# HolmesAndWatchson-BASIC-TOP.net
KiCad netlist of a schematic drawn in EAGLE
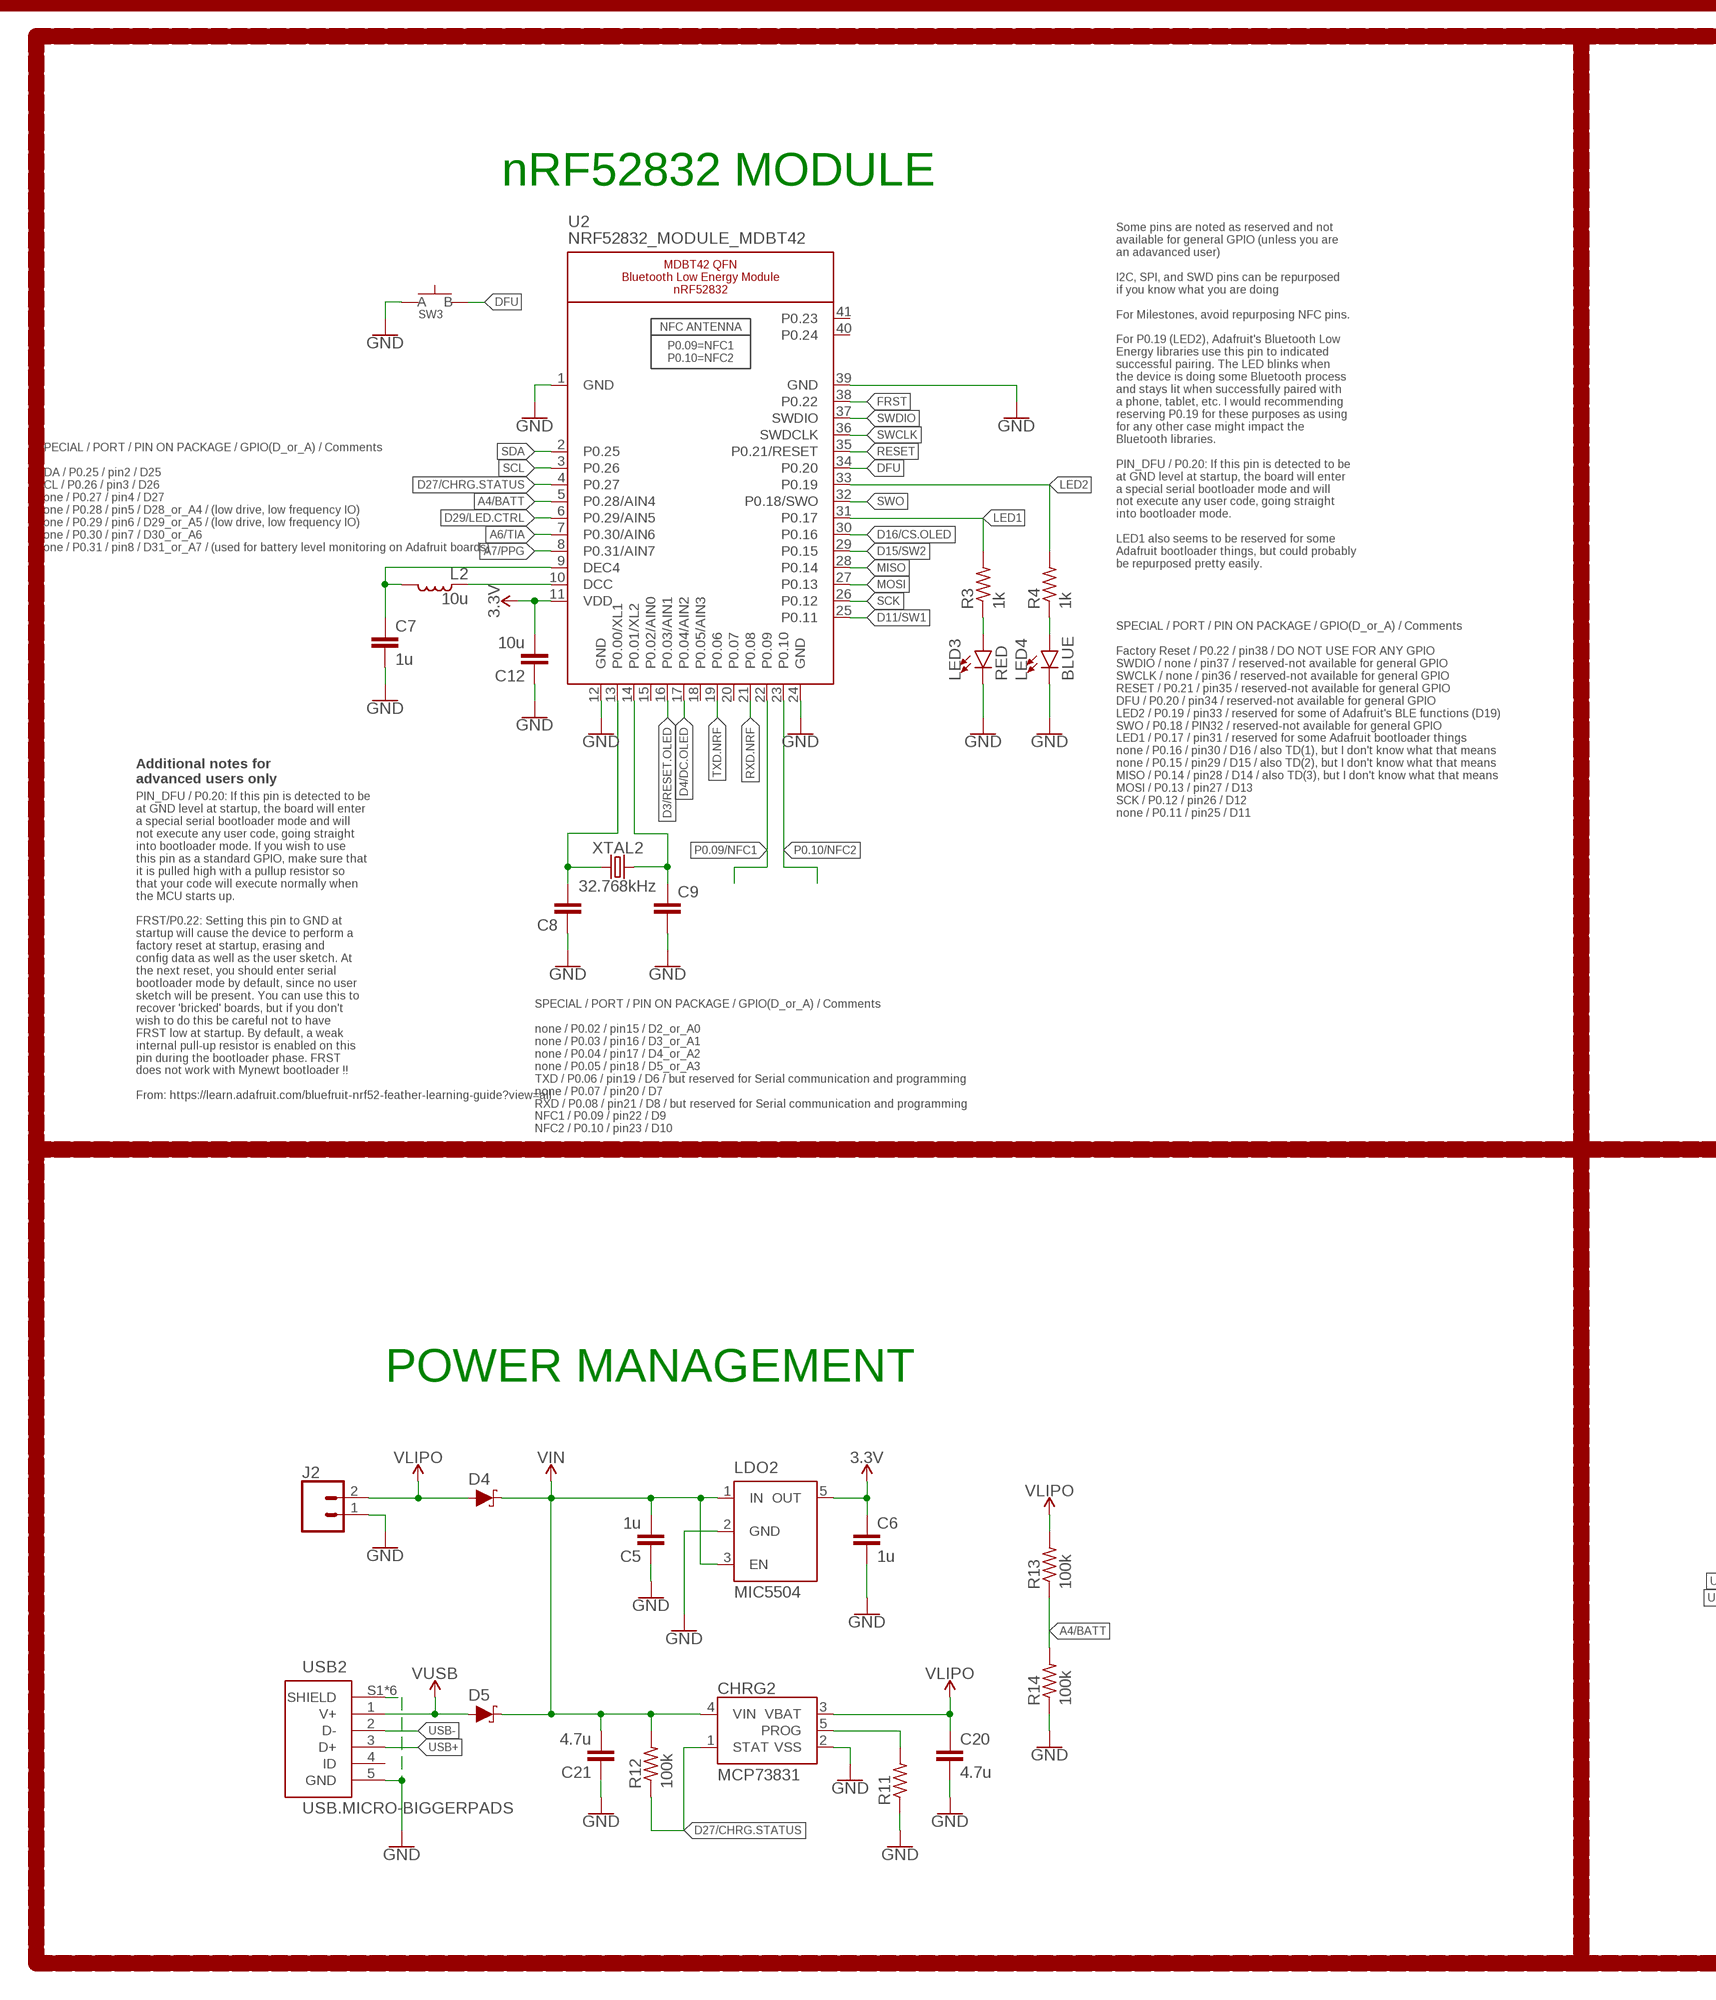
[diagram p0: schematic, sheet 1, part 1 of 2]
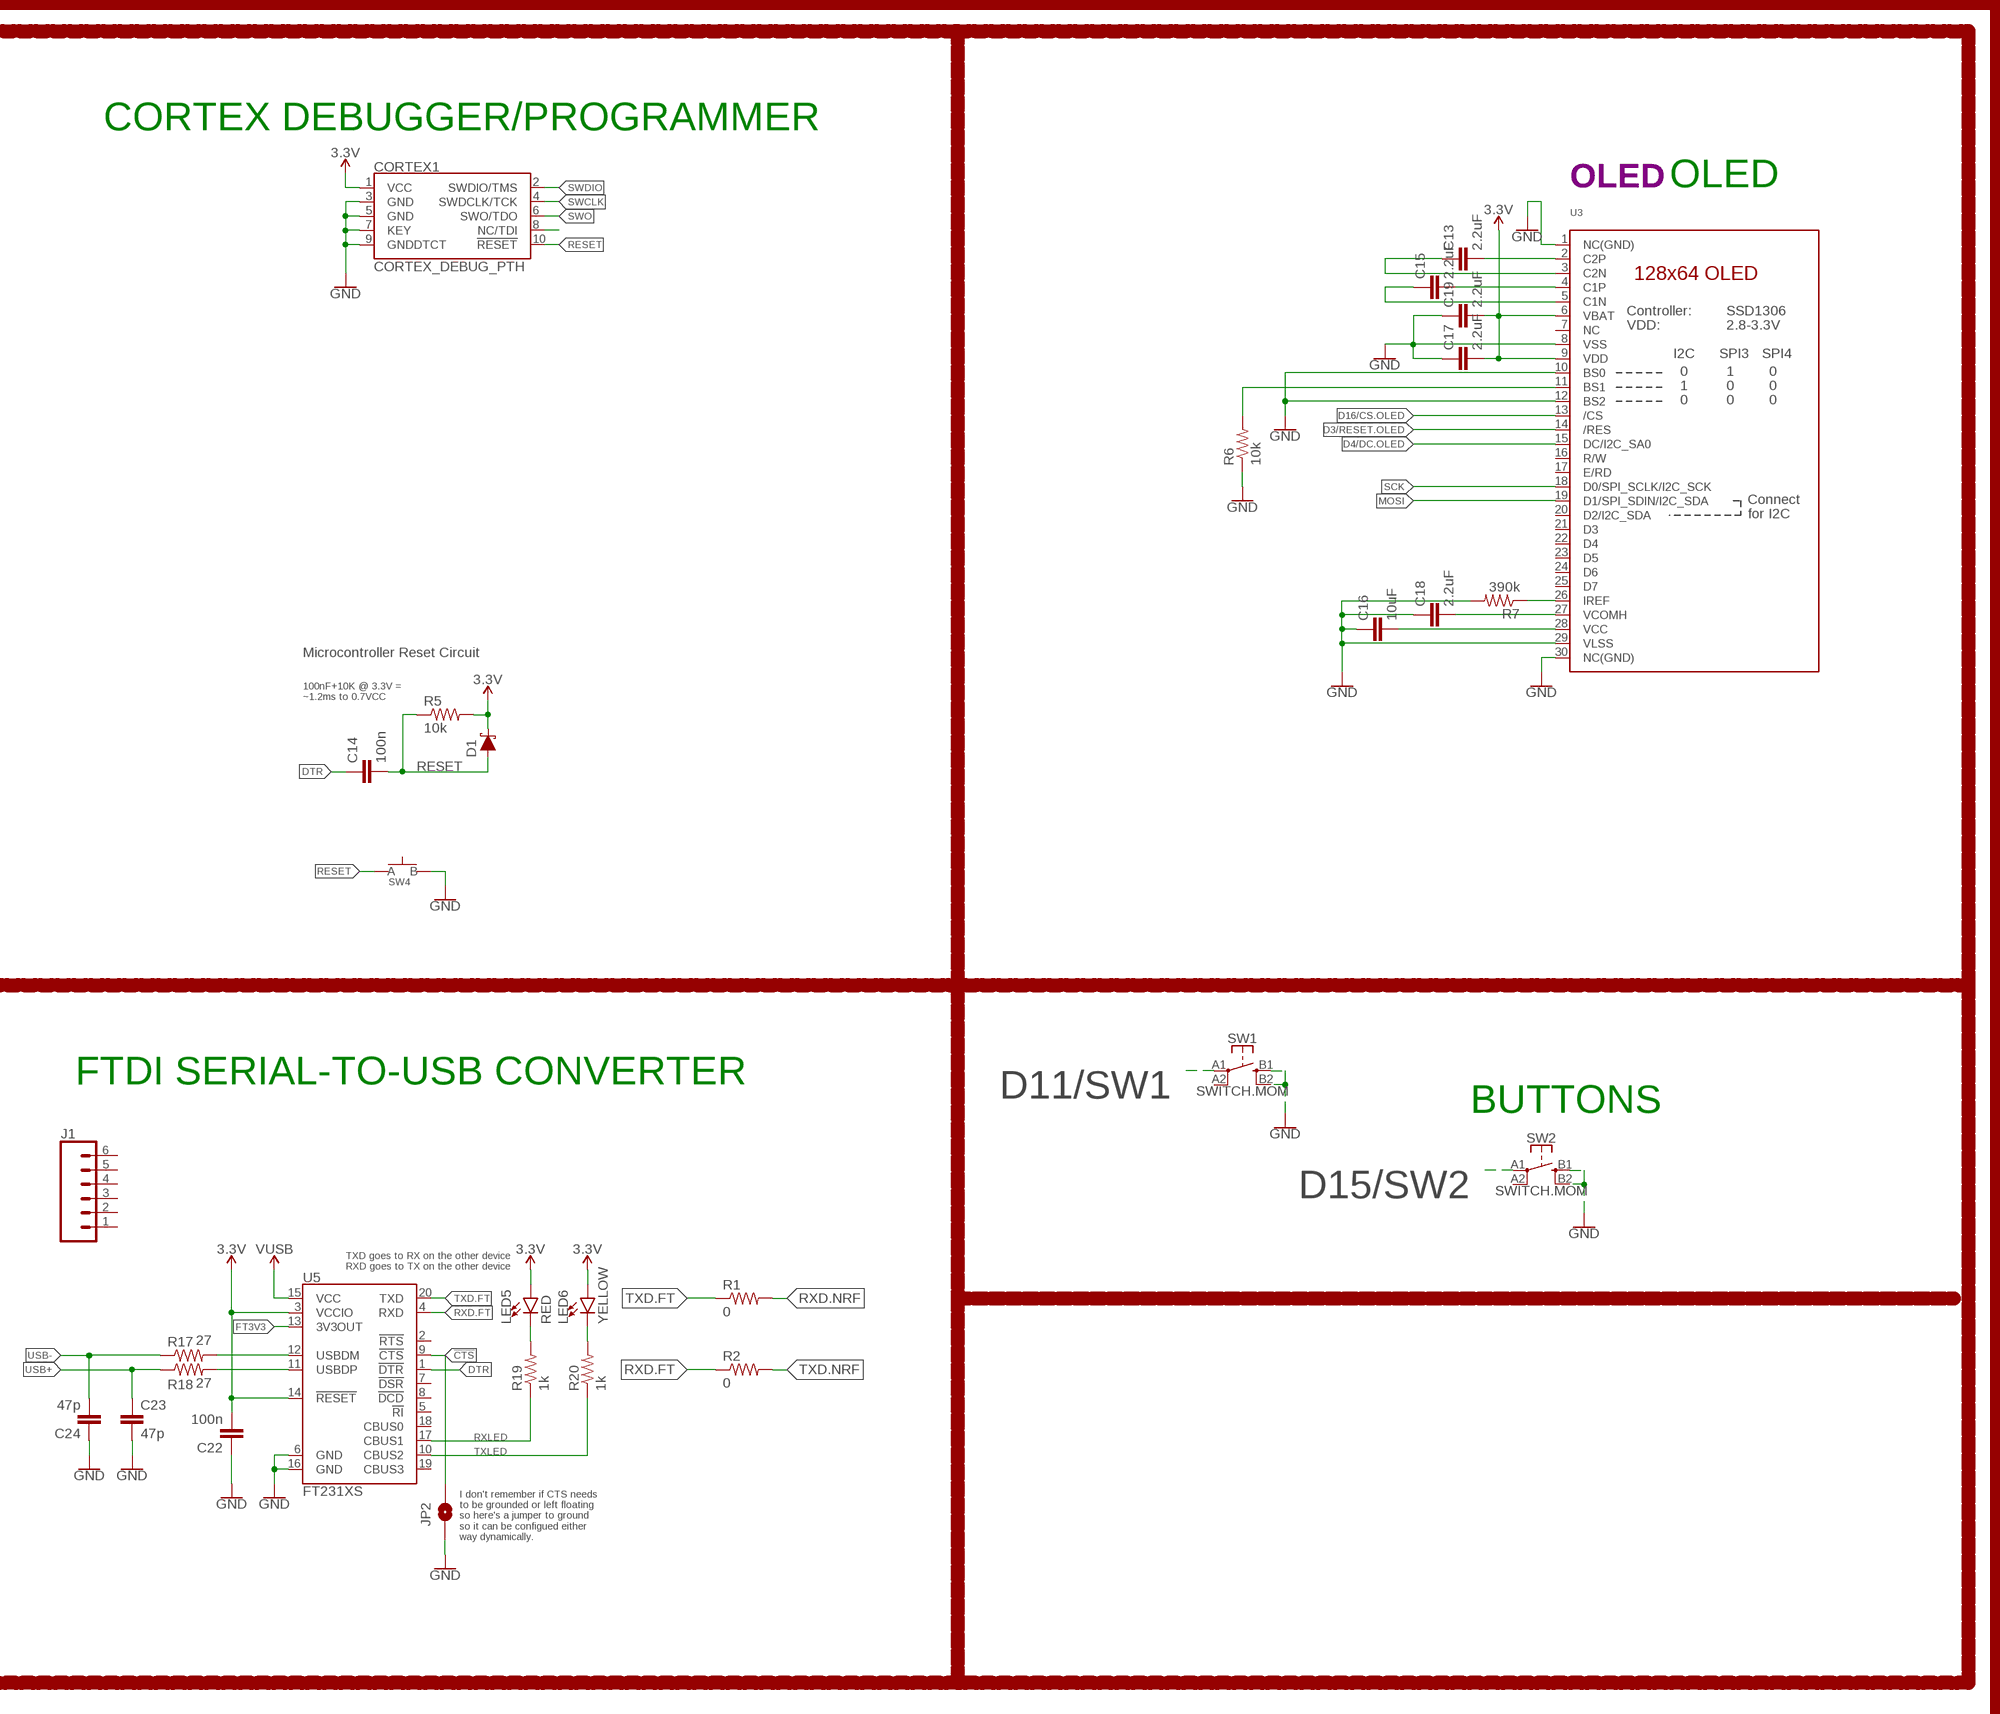
[diagram p1: schematic, sheet 1, part 2 of 2]

(export (version "E")
  (design (tool "Eeschema 10.0.6"))
  (components
    (comp (ref "C5")
      (value "1u")
      (footprint "eagle-import:C0603")
      (libsource (lib "eagle-import") (part "CAPACITOR0603"))
    )
    (comp (ref "C6")
      (value "1u")
      (footprint "eagle-import:C0603")
      (libsource (lib "eagle-import") (part "CAPACITOR0603"))
    )
    (comp (ref "C7")
      (value "1u")
      (footprint "eagle-import:C0603")
      (libsource (lib "eagle-import") (part "CAPACITOR0603"))
    )
    (comp (ref "C8")
      (value "CAPACITOR0603")
      (footprint "eagle-import:C0603")
      (libsource (lib "eagle-import") (part "CAPACITOR0603"))
    )
    (comp (ref "C9")
      (value "CAPACITOR0603")
      (footprint "eagle-import:C0603")
      (libsource (lib "eagle-import") (part "CAPACITOR0603"))
    )
    (comp (ref "C12")
      (value "10u")
      (footprint "eagle-import:C0805")
      (libsource (lib "eagle-import") (part "CAPACITOR0805"))
    )
    (comp (ref "C13")
      (value "2.2uF")
      (footprint "eagle-import:C0402")
      (libsource (lib "eagle-import") (part "CAPACITOR0402"))
    )
    (comp (ref "C14")
      (value "100n")
      (footprint "eagle-import:C0603")
      (libsource (lib "eagle-import") (part "CAPACITOR0603"))
    )
    (comp (ref "C15")
      (value "2.2uF")
      (footprint "eagle-import:C0402")
      (libsource (lib "eagle-import") (part "CAPACITOR0402"))
    )
    (comp (ref "C16")
      (value "10uF")
      (footprint "eagle-import:C0603")
      (libsource (lib "eagle-import") (part "CAPACITOR0603"))
    )
    (comp (ref "C17")
      (value "2.2uF")
      (footprint "eagle-import:C0402")
      (libsource (lib "eagle-import") (part "CAPACITOR0402"))
    )
    (comp (ref "C18")
      (value "2.2uF")
      (footprint "eagle-import:C0402")
      (libsource (lib "eagle-import") (part "CAPACITOR0402"))
    )
    (comp (ref "C19")
      (value "2.2uF")
      (footprint "eagle-import:C0402")
      (libsource (lib "eagle-import") (part "CAPACITOR0402"))
    )
    (comp (ref "C20")
      (value "4.7u")
      (footprint "eagle-import:C0603")
      (libsource (lib "eagle-import") (part "CAPACITOR0603"))
    )
    (comp (ref "C21")
      (value "4.7u")
      (footprint "eagle-import:C0603")
      (libsource (lib "eagle-import") (part "CAPACITOR0603"))
    )
    (comp (ref "C22")
      (value "100n")
      (footprint "eagle-import:C0603")
      (libsource (lib "eagle-import") (part "CAPACITOR0603"))
    )
    (comp (ref "C23")
      (value "47p")
      (footprint "eagle-import:C0603")
      (libsource (lib "eagle-import") (part "CAPACITOR0603"))
    )
    (comp (ref "C24")
      (value "47p")
      (footprint "eagle-import:C0603")
      (libsource (lib "eagle-import") (part "CAPACITOR0603"))
    )
    (comp (ref "CHRG2")
      (value "MCP73831")
      (footprint "eagle-import:SOT23-5")
      (libsource (lib "eagle-import") (part "MCP73831"))
    )
    (comp (ref "CORTEX1")
      (value "CORTEX_DEBUG_PTH")
      (footprint "eagle-import:2X5-PTH-1.27MM")
      (libsource (lib "eagle-import") (part "CORTEX_DEBUG_PTH"))
    )
    (comp (ref "D1")
      (value "SCHOTTKY-USC")
      (footprint "eagle-import:USC")
      (libsource (lib "eagle-import") (part "SCHOTTKY-USC"))
    )
    (comp (ref "D4")
      (value "SCHOTTKY-USC")
      (footprint "eagle-import:USC")
      (libsource (lib "eagle-import") (part "SCHOTTKY-USC"))
    )
    (comp (ref "D5")
      (value "SCHOTTKY-USC")
      (footprint "eagle-import:USC")
      (libsource (lib "eagle-import") (part "SCHOTTKY-USC"))
    )
    (comp (ref "J1")
      (value "CONN_061.27MM")
      (footprint "eagle-import:1X06_1.27MM")
      (libsource (lib "eagle-import") (part "CONN_061.27MM"))
    )
    (comp (ref "J2")
      (value "CONN_02")
      (footprint "eagle-import:1X02")
      (libsource (lib "eagle-import") (part "CONN_02"))
    )
    (comp (ref "JP2")
      (value "JUMPER-SMT_2_NO_SILK")
      (footprint "eagle-import:SMT-JUMPER_2_NO_SILK")
      (libsource (lib "eagle-import") (part "JUMPER-SMT_2_NO_SILK"))
    )
    (comp (ref "L2")
      (value "10u")
      (footprint "eagle-import:L0603")
      (libsource (lib "eagle-import") (part "INDUCTOR0603"))
    )
    (comp (ref "LDO2")
      (value "MIC5504")
      (footprint "eagle-import:SOT23-5")
      (libsource (lib "eagle-import") (part "MIC5504"))
    )
    (comp (ref "LED3")
      (value "RED")
      (footprint "eagle-import:LED-0603")
      (libsource (lib "eagle-import") (part "LED0603"))
    )
    (comp (ref "LED4")
      (value "BLUE")
      (footprint "eagle-import:LED-0603")
      (libsource (lib "eagle-import") (part "LED0603"))
    )
    (comp (ref "LED5")
      (value "RED")
      (footprint "eagle-import:LED-0603")
      (libsource (lib "eagle-import") (part "LED0603"))
    )
    (comp (ref "LED6")
      (value "YELLOW")
      (footprint "eagle-import:LED-0603")
      (libsource (lib "eagle-import") (part "LED0603"))
    )
    (comp (ref "R1")
      (value "0")
      (footprint "eagle-import:R0603")
      (libsource (lib "eagle-import") (part "RESISTOR0603"))
    )
    (comp (ref "R2")
      (value "0")
      (footprint "eagle-import:R0603")
      (libsource (lib "eagle-import") (part "RESISTOR0603"))
    )
    (comp (ref "R3")
      (value "1k")
      (footprint "eagle-import:R0603")
      (libsource (lib "eagle-import") (part "RESISTOR0603"))
    )
    (comp (ref "R4")
      (value "1k")
      (footprint "eagle-import:R0603")
      (libsource (lib "eagle-import") (part "RESISTOR0603"))
    )
    (comp (ref "R5")
      (value "10k")
      (footprint "eagle-import:R0603")
      (libsource (lib "eagle-import") (part "RESISTOR0603"))
    )
    (comp (ref "R6")
      (value "10k")
      (footprint "eagle-import:R0603")
      (libsource (lib "eagle-import") (part "RESISTOR0603"))
    )
    (comp (ref "R7")
      (value "390k")
      (footprint "eagle-import:R0603")
      (libsource (lib "eagle-import") (part "RESISTOR0603"))
    )
    (comp (ref "R11")
      (value "RESISTOR0603")
      (footprint "eagle-import:R0603")
      (libsource (lib "eagle-import") (part "RESISTOR0603"))
    )
    (comp (ref "R12")
      (value "100k")
      (footprint "eagle-import:R0603")
      (libsource (lib "eagle-import") (part "RESISTOR0603"))
    )
    (comp (ref "R13")
      (value "100k")
      (footprint "eagle-import:R0603")
      (libsource (lib "eagle-import") (part "RESISTOR0603"))
    )
    (comp (ref "R14")
      (value "100k")
      (footprint "eagle-import:R0603")
      (libsource (lib "eagle-import") (part "RESISTOR0603"))
    )
    (comp (ref "R17")
      (value "27")
      (footprint "eagle-import:R0603")
      (libsource (lib "eagle-import") (part "RESISTOR0603"))
    )
    (comp (ref "R18")
      (value "27")
      (footprint "eagle-import:R0603")
      (libsource (lib "eagle-import") (part "RESISTOR0603"))
    )
    (comp (ref "R19")
      (value "1k")
      (footprint "eagle-import:R0603")
      (libsource (lib "eagle-import") (part "RESISTOR0603"))
    )
    (comp (ref "R20")
      (value "1k")
      (footprint "eagle-import:R0603")
      (libsource (lib "eagle-import") (part "RESISTOR0603"))
    )
    (comp (ref "SW1")
      (value "SWITCH.MOM")
      (footprint "eagle-import:TACTILE_SWITCH_SMD_6.2MM_TALL")
      (libsource (lib "eagle-import") (part "SWITCH.MOM"))
    )
    (comp (ref "SW2")
      (value "SWITCH.MOM")
      (footprint "eagle-import:TACTILE_SWITCH_SMD_6.2MM_TALL")
      (libsource (lib "eagle-import") (part "SWITCH.MOM"))
    )
    (comp (ref "SW3")
      (value "SPST-PTS830GG140-COPY.1-3")
      (footprint "eagle-import:BUTTON-GULLWING")
      (libsource (lib "eagle-import") (part "SPST-PTS830GG140-COPY.1-3"))
    )
    (comp (ref "SW4")
      (value "SPST-PTS830GG140-COPY.1-3")
      (footprint "eagle-import:BUTTON-GULLWING")
      (libsource (lib "eagle-import") (part "SPST-PTS830GG140-COPY.1-3"))
    )
    (comp (ref "U2")
      (value "NRF52832_MODULE_MDBT42")
      (footprint "eagle-import:BLE_MODULE_RAYTAC_MDBT42")
      (libsource (lib "eagle-import") (part "NRF52832_MODULE_MDBT42"))
    )
    (comp (ref "U3")
      (value "DISP_OLED_UG-2864HSWEG01-NO-WRAPAROUND")
      (footprint "eagle-import:UG-2864HSWEG01_0.96IN_NO-WRAPAROUND")
      (libsource (lib "eagle-import") (part "DISP_OLED_UG-2864HSWEG01-NO-WRAPAROUND"))
    )
    (comp (ref "U5")
      (value "FT231XS")
      (footprint "eagle-import:SSOP20_L")
      (libsource (lib "eagle-import") (part "FT231XS"))
    )
    (comp (ref "USB2")
      (value "USB.MICRO-BIGGERPADS")
      (footprint "eagle-import:USB-MICRO-01.BIGGERPADS")
      (libsource (lib "eagle-import") (part "USB.MICRO-BIGGERPADS"))
    )
    (comp (ref "XTAL2")
      (value "32.768kHz")
      (footprint "eagle-import:2-SMD.NOLEAD.2.0MMTO1.2MM")
      (libsource (lib "eagle-import") (part "CRYSTALECS-.327-12.5-12-C-TR"))
    )
  )
  (nets
    (net (code "1") (name "/RXLED") (class "Default")
      (node (ref "R19") (pin "1") (pinfunction "1_1") (pintype "passive"))
      (node (ref "U5") (pin "17") (pinfunction "CBUS1_17") (pintype "bidirectional"))
    )
    (net (code "2") (name "/TXLED") (class "Default")
      (node (ref "R20") (pin "1") (pinfunction "1_1") (pintype "passive"))
      (node (ref "U5") (pin "10") (pinfunction "CBUS2_10") (pintype "bidirectional"))
    )
    (net (code "3") (name "/~{CTS}") (class "Default")
      (node (ref "JP2") (pin "2") (pinfunction "2_2") (pintype "passive"))
      (node (ref "U5") (pin "9") (pinfunction "~{CTS}_9") (pintype "bidirectional"))
    )
    (net (code "4") (name "3.3V") (class "Default")
      (node (ref "C12") (pin "2") (pinfunction "2_2") (pintype "passive"))
      (node (ref "C17") (pin "2") (pinfunction "2_2") (pintype "passive"))
      (node (ref "C19") (pin "2") (pinfunction "2_2") (pintype "passive"))
      (node (ref "C22") (pin "2") (pinfunction "2_2") (pintype "passive"))
      (node (ref "C6") (pin "1") (pinfunction "1_1") (pintype "passive"))
      (node (ref "CORTEX1") (pin "1") (pinfunction "VCC_1") (pintype "bidirectional"))
      (node (ref "D1") (pin "-") (pinfunction "C_-") (pintype "passive"))
      (node (ref "LDO2") (pin "5") (pinfunction "OUT_5") (pintype "bidirectional"))
      (node (ref "LED5") (pin "A") (pinfunction "A_A") (pintype "passive"))
      (node (ref "LED6") (pin "A") (pinfunction "A_A") (pintype "passive"))
      (node (ref "R5") (pin "2") (pinfunction "2_2") (pintype "passive"))
      (node (ref "U2") (pin "11") (pinfunction "VDD_11") (pintype "bidirectional"))
      (node (ref "U3") (pin "6") (pinfunction "VBAT_6") (pintype "input"))
      (node (ref "U3") (pin "9") (pinfunction "VDD_9") (pintype "power_in"))
      (node (ref "U5") (pin "14") (pinfunction "~{RESET}_14") (pintype "bidirectional"))
      (node (ref "U5") (pin "3") (pinfunction "VCCIO_3") (pintype "bidirectional"))
    )
    (net (code "5") (name "A4{slash}BATT") (class "Default")
      (node (ref "R13") (pin "1") (pinfunction "1_1") (pintype "passive"))
      (node (ref "R14") (pin "2") (pinfunction "2_2") (pintype "passive"))
      (node (ref "U2") (pin "5") (pinfunction "P0.28/AIN4_5") (pintype "bidirectional"))
    )
    (net (code "6") (name "A6{slash}TIA") (class "Default")
      (node (ref "U2") (pin "7") (pinfunction "P0.30/AIN6_7") (pintype "bidirectional"))
    )
    (net (code "7") (name "A7{slash}PPG") (class "Default")
      (node (ref "U2") (pin "8") (pinfunction "P0.31/AIN7_8") (pintype "bidirectional"))
    )
    (net (code "8") (name "D3{slash}RESET.OLED") (class "Default")
      (node (ref "U2") (pin "16") (pinfunction "P0.03/AIN1_16") (pintype "bidirectional"))
      (node (ref "U3") (pin "14") (pinfunction "/RES_14") (pintype "input"))
    )
    (net (code "9") (name "D4{slash}DC.OLED") (class "Default")
      (node (ref "U2") (pin "17") (pinfunction "P0.04/AIN2_17") (pintype "bidirectional"))
      (node (ref "U3") (pin "15") (pinfunction "DC/I2C_SA0_15") (pintype "input"))
    )
    (net (code "10") (name "D11{slash}SW1") (class "Default")
      (node (ref "SW1") (pin "A1") (pinfunction "1_A1") (pintype "passive"))
      (node (ref "U2") (pin "25") (pinfunction "P0.11_25") (pintype "bidirectional"))
    )
    (net (code "11") (name "D15{slash}SW2") (class "Default")
      (node (ref "SW2") (pin "A1") (pinfunction "1_A1") (pintype "passive"))
      (node (ref "U2") (pin "29") (pinfunction "P0.15_29") (pintype "bidirectional"))
    )
    (net (code "12") (name "D16{slash}CS.OLED") (class "Default")
      (node (ref "U2") (pin "30") (pinfunction "P0.16_30") (pintype "bidirectional"))
      (node (ref "U3") (pin "13") (pinfunction "/CS_13") (pintype "input"))
    )
    (net (code "13") (name "D27{slash}CHRG.STATUS") (class "Default")
      (node (ref "CHRG2") (pin "1") (pinfunction "STAT_1") (pintype "output"))
      (node (ref "R12") (pin "1") (pinfunction "1_1") (pintype "passive"))
      (node (ref "U2") (pin "4") (pinfunction "P0.27_4") (pintype "bidirectional"))
    )
    (net (code "14") (name "D29{slash}LED.CTRL") (class "Default")
      (node (ref "U2") (pin "6") (pinfunction "P0.29/AIN5_6") (pintype "bidirectional"))
    )
    (net (code "15") (name "DFU") (class "Default")
      (node (ref "SW3") (pin "3") (pinfunction "B_3") (pintype "bidirectional"))
      (node (ref "U2") (pin "34") (pinfunction "P0.20_34") (pintype "bidirectional"))
    )
    (net (code "16") (name "DTR") (class "Default")
      (node (ref "C14") (pin "1") (pinfunction "1_1") (pintype "passive"))
      (node (ref "U5") (pin "1") (pinfunction "~{DTR}_1") (pintype "bidirectional"))
    )
    (net (code "17") (name "FRST") (class "Default")
      (node (ref "U2") (pin "38") (pinfunction "P0.22_38") (pintype "bidirectional"))
    )
    (net (code "18") (name "FT3V3") (class "Default")
      (node (ref "U5") (pin "13") (pinfunction "3V3OUT_13") (pintype "bidirectional"))
    )
    (net (code "19") (name "GND") (class "Default")
      (node (ref "C12") (pin "1") (pinfunction "1_1") (pintype "passive"))
      (node (ref "C16") (pin "1") (pinfunction "1_1") (pintype "passive"))
      (node (ref "C17") (pin "1") (pinfunction "1_1") (pintype "passive"))
      (node (ref "C18") (pin "1") (pinfunction "1_1") (pintype "passive"))
      (node (ref "C19") (pin "1") (pinfunction "1_1") (pintype "passive"))
      (node (ref "C20") (pin "2") (pinfunction "2_2") (pintype "passive"))
      (node (ref "C21") (pin "1") (pinfunction "1_1") (pintype "passive"))
      (node (ref "C22") (pin "1") (pinfunction "1_1") (pintype "passive"))
      (node (ref "C23") (pin "2") (pinfunction "2_2") (pintype "passive"))
      (node (ref "C24") (pin "1") (pinfunction "1_1") (pintype "passive"))
      (node (ref "C5") (pin "1") (pinfunction "1_1") (pintype "passive"))
      (node (ref "C6") (pin "2") (pinfunction "2_2") (pintype "passive"))
      (node (ref "C7") (pin "2") (pinfunction "2_2") (pintype "passive"))
      (node (ref "C8") (pin "1") (pinfunction "1_1") (pintype "passive"))
      (node (ref "C9") (pin "2") (pinfunction "2_2") (pintype "passive"))
      (node (ref "CHRG2") (pin "2") (pinfunction "VSS_2") (pintype "power_in"))
      (node (ref "CORTEX1") (pin "3") (pinfunction "GND_3") (pintype "bidirectional"))
      (node (ref "CORTEX1") (pin "5") (pinfunction "GND_5") (pintype "bidirectional"))
      (node (ref "CORTEX1") (pin "7") (pinfunction "KEY_7") (pintype "bidirectional"))
      (node (ref "CORTEX1") (pin "9") (pinfunction "GNDDTCT_9") (pintype "bidirectional"))
      (node (ref "J2") (pin "1") (pinfunction "1_1") (pintype "passive"))
      (node (ref "JP2") (pin "1") (pinfunction "1_1") (pintype "passive"))
      (node (ref "LDO2") (pin "2") (pinfunction "GND_2") (pintype "bidirectional"))
      (node (ref "LED3") (pin "C") (pinfunction "C_C") (pintype "passive"))
      (node (ref "LED4") (pin "C") (pinfunction "C_C") (pintype "passive"))
      (node (ref "R11") (pin "1") (pinfunction "1_1") (pintype "passive"))
      (node (ref "R14") (pin "1") (pinfunction "1_1") (pintype "passive"))
      (node (ref "R6") (pin "1") (pinfunction "1_1") (pintype "passive"))
      (node (ref "R7") (pin "2") (pinfunction "2_2") (pintype "passive"))
      (node (ref "SW1") (pin "B1") (pinfunction "3_B1") (pintype "passive"))
      (node (ref "SW1") (pin "B2") (pinfunction "4_B2") (pintype "passive"))
      (node (ref "SW2") (pin "B1") (pinfunction "3_B1") (pintype "passive"))
      (node (ref "SW2") (pin "B2") (pinfunction "4_B2") (pintype "passive"))
      (node (ref "SW3") (pin "1") (pinfunction "A_1") (pintype "bidirectional"))
      (node (ref "SW4") (pin "3") (pinfunction "B_3") (pintype "bidirectional"))
      (node (ref "U2") (pin "1") (pinfunction "GND_1") (pintype "bidirectional"))
      (node (ref "U2") (pin "12") (pinfunction "GND_12") (pintype "bidirectional"))
      (node (ref "U2") (pin "24") (pinfunction "GND_24") (pintype "bidirectional"))
      (node (ref "U2") (pin "39") (pinfunction "GND_39") (pintype "bidirectional"))
      (node (ref "U3") (pin "1") (pinfunction "NC(GND)_1") (pintype "input"))
      (node (ref "U3") (pin "10") (pinfunction "BS0_10") (pintype "input"))
      (node (ref "U3") (pin "12") (pinfunction "BS2_12") (pintype "input"))
      (node (ref "U3") (pin "29") (pinfunction "VLSS_29") (pintype "power_in"))
      (node (ref "U3") (pin "30") (pinfunction "NC(GND)_30") (pintype "input"))
      (node (ref "U3") (pin "8") (pinfunction "VSS_8") (pintype "power_in"))
      (node (ref "U5") (pin "16") (pinfunction "GND_16") (pintype "bidirectional"))
      (node (ref "U5") (pin "6") (pinfunction "GND_6") (pintype "bidirectional"))
      (node (ref "USB2") (pin "5") (pinfunction "GND_5") (pintype "bidirectional"))
      (node (ref "USB2") (pin "S1") (pinfunction "SHIELD_S1") (pintype "bidirectional"))
      (node (ref "USB2") (pin "S2") (pinfunction "SHIELD_S2") (pintype "bidirectional"))
      (node (ref "USB2") (pin "S3") (pinfunction "SHIELD_S3") (pintype "bidirectional"))
      (node (ref "USB2") (pin "S4") (pinfunction "SHIELD_S4") (pintype "bidirectional"))
      (node (ref "USB2") (pin "S5") (pinfunction "SHIELD_S5") (pintype "bidirectional"))
      (node (ref "USB2") (pin "S6") (pinfunction "SHIELD_S6") (pintype "bidirectional"))
    )
    (net (code "20") (name "LED1") (class "Default")
      (node (ref "R3") (pin "2") (pinfunction "2_2") (pintype "passive"))
      (node (ref "U2") (pin "31") (pinfunction "P0.17_31") (pintype "bidirectional"))
    )
    (net (code "21") (name "LED2") (class "Default")
      (node (ref "R4") (pin "2") (pinfunction "2_2") (pintype "passive"))
      (node (ref "U2") (pin "33") (pinfunction "P0.19_33") (pintype "bidirectional"))
    )
    (net (code "22") (name "MISO") (class "Default")
      (node (ref "U2") (pin "28") (pinfunction "P0.14_28") (pintype "bidirectional"))
    )
    (net (code "23") (name "MOSI") (class "Default")
      (node (ref "U2") (pin "27") (pinfunction "P0.13_27") (pintype "bidirectional"))
      (node (ref "U3") (pin "19") (pinfunction "D1/SPI_SDIN/I2C_SDA_19") (pintype "bidirectional"))
    )
    (net (code "24") (name "Net-(CHRG2-PROG)") (class "Default")
      (node (ref "CHRG2") (pin "5") (pinfunction "PROG_5") (pintype "input"))
      (node (ref "R11") (pin "2") (pinfunction "2_2") (pintype "passive"))
    )
    (net (code "25") (name "Net-(LED3-PadA)") (class "Default")
      (node (ref "LED3") (pin "A") (pinfunction "A_A") (pintype "passive"))
      (node (ref "R3") (pin "1") (pinfunction "1_1") (pintype "passive"))
    )
    (net (code "26") (name "Net-(LED4-PadA)") (class "Default")
      (node (ref "LED4") (pin "A") (pinfunction "A_A") (pintype "passive"))
      (node (ref "R4") (pin "1") (pinfunction "1_1") (pintype "passive"))
    )
    (net (code "27") (name "Net-(LED5-PadC)") (class "Default")
      (node (ref "LED5") (pin "C") (pinfunction "C_C") (pintype "passive"))
      (node (ref "R19") (pin "2") (pinfunction "2_2") (pintype "passive"))
    )
    (net (code "28") (name "Net-(LED6-PadC)") (class "Default")
      (node (ref "LED6") (pin "C") (pinfunction "C_C") (pintype "passive"))
      (node (ref "R20") (pin "2") (pinfunction "2_2") (pintype "passive"))
    )
    (net (code "29") (name "Net-(U2-DCC)") (class "Default")
      (node (ref "L2") (pin "1") (pinfunction "1_1") (pintype "passive"))
      (node (ref "U2") (pin "10") (pinfunction "DCC_10") (pintype "bidirectional"))
    )
    (net (code "30") (name "Net-(U2-DEC4)") (class "Default")
      (node (ref "C7") (pin "1") (pinfunction "1_1") (pintype "passive"))
      (node (ref "L2") (pin "2") (pinfunction "2_2") (pintype "passive"))
      (node (ref "U2") (pin "9") (pinfunction "DEC4_9") (pintype "bidirectional"))
    )
    (net (code "31") (name "Net-(U2-P0.00{slash}XL1)") (class "Default")
      (node (ref "C8") (pin "2") (pinfunction "2_2") (pintype "passive"))
      (node (ref "U2") (pin "13") (pinfunction "P0.00/XL1_13") (pintype "bidirectional"))
      (node (ref "XTAL2") (pin "P$1") (pinfunction "1_P$1") (pintype "passive"))
    )
    (net (code "32") (name "Net-(U2-P0.01{slash}XL2)") (class "Default")
      (node (ref "C9") (pin "1") (pinfunction "1_1") (pintype "passive"))
      (node (ref "U2") (pin "14") (pinfunction "P0.01/XL2_14") (pintype "bidirectional"))
      (node (ref "XTAL2") (pin "P$2") (pinfunction "2_P$2") (pintype "passive"))
    )
    (net (code "33") (name "Net-(U3-BS1)") (class "Default")
      (node (ref "R6") (pin "2") (pinfunction "2_2") (pintype "passive"))
      (node (ref "U3") (pin "11") (pinfunction "BS1_11") (pintype "input"))
    )
    (net (code "34") (name "Net-(U3-C1N)") (class "Default")
      (node (ref "C15") (pin "1") (pinfunction "1_1") (pintype "passive"))
      (node (ref "U3") (pin "5") (pinfunction "C1N_5") (pintype "input"))
    )
    (net (code "35") (name "Net-(U3-C1P)") (class "Default")
      (node (ref "C15") (pin "2") (pinfunction "2_2") (pintype "passive"))
      (node (ref "U3") (pin "4") (pinfunction "C1P_4") (pintype "input"))
    )
    (net (code "36") (name "Net-(U3-C2N)") (class "Default")
      (node (ref "C13") (pin "1") (pinfunction "1_1") (pintype "passive"))
      (node (ref "U3") (pin "3") (pinfunction "C2N_3") (pintype "input"))
    )
    (net (code "37") (name "Net-(U3-C2P)") (class "Default")
      (node (ref "C13") (pin "2") (pinfunction "2_2") (pintype "passive"))
      (node (ref "U3") (pin "2") (pinfunction "C2P_2") (pintype "input"))
    )
    (net (code "38") (name "Net-(U3-IREF)") (class "Default")
      (node (ref "R7") (pin "1") (pinfunction "1_1") (pintype "passive"))
      (node (ref "U3") (pin "26") (pinfunction "IREF_26") (pintype "input"))
    )
    (net (code "39") (name "Net-(U3-VCC)") (class "Default")
      (node (ref "C16") (pin "2") (pinfunction "2_2") (pintype "passive"))
      (node (ref "U3") (pin "28") (pinfunction "VCC_28") (pintype "power_in"))
    )
    (net (code "40") (name "Net-(U3-VCOMH)") (class "Default")
      (node (ref "C18") (pin "2") (pinfunction "2_2") (pintype "passive"))
      (node (ref "U3") (pin "27") (pinfunction "VCOMH_27") (pintype "output"))
    )
    (net (code "41") (name "Net-(U5-USBDM)") (class "Default")
      (node (ref "R17") (pin "2") (pinfunction "2_2") (pintype "passive"))
      (node (ref "U5") (pin "12") (pinfunction "USBDM_12") (pintype "bidirectional"))
    )
    (net (code "42") (name "Net-(U5-USBDP)") (class "Default")
      (node (ref "R18") (pin "2") (pinfunction "2_2") (pintype "passive"))
      (node (ref "U5") (pin "11") (pinfunction "USBDP_11") (pintype "bidirectional"))
    )
    (net (code "43") (name "P0.09{slash}NFC1") (class "Default")
      (node (ref "U2") (pin "22") (pinfunction "P0.09_22") (pintype "bidirectional"))
    )
    (net (code "44") (name "P0.10{slash}NFC2") (class "Default")
      (node (ref "U2") (pin "23") (pinfunction "P0.10_23") (pintype "bidirectional"))
    )
    (net (code "45") (name "RESET") (class "Default")
      (node (ref "C14") (pin "2") (pinfunction "2_2") (pintype "passive"))
      (node (ref "CORTEX1") (pin "10") (pinfunction "~{RESET}_10") (pintype "bidirectional"))
      (node (ref "D1") (pin "+") (pinfunction "A_+") (pintype "passive"))
      (node (ref "R5") (pin "1") (pinfunction "1_1") (pintype "passive"))
      (node (ref "SW4") (pin "1") (pinfunction "A_1") (pintype "bidirectional"))
      (node (ref "U2") (pin "35") (pinfunction "P0.21/RESET_35") (pintype "bidirectional"))
    )
    (net (code "46") (name "RXD.FT") (class "Default")
      (node (ref "R2") (pin "1") (pinfunction "1_1") (pintype "passive"))
      (node (ref "U5") (pin "4") (pinfunction "RXD_4") (pintype "bidirectional"))
    )
    (net (code "47") (name "RXD.NRF") (class "Default")
      (node (ref "R1") (pin "2") (pinfunction "2_2") (pintype "passive"))
      (node (ref "U2") (pin "21") (pinfunction "P0.08_21") (pintype "bidirectional"))
    )
    (net (code "48") (name "SCK") (class "Default")
      (node (ref "U2") (pin "26") (pinfunction "P0.12_26") (pintype "bidirectional"))
      (node (ref "U3") (pin "18") (pinfunction "D0/SPI_SCLK/I2C_SCK_18") (pintype "bidirectional"))
    )
    (net (code "49") (name "SCL") (class "Default")
      (node (ref "U2") (pin "3") (pinfunction "P0.26_3") (pintype "bidirectional"))
    )
    (net (code "50") (name "SDA") (class "Default")
      (node (ref "U2") (pin "2") (pinfunction "P0.25_2") (pintype "bidirectional"))
    )
    (net (code "51") (name "SWCLK") (class "Default")
      (node (ref "CORTEX1") (pin "4") (pinfunction "SWDCLK/TCK_4") (pintype "bidirectional"))
      (node (ref "U2") (pin "36") (pinfunction "SWDCLK_36") (pintype "bidirectional"))
    )
    (net (code "52") (name "SWDIO") (class "Default")
      (node (ref "CORTEX1") (pin "2") (pinfunction "SWDIO/TMS_2") (pintype "bidirectional"))
      (node (ref "U2") (pin "37") (pinfunction "SWDIO_37") (pintype "bidirectional"))
    )
    (net (code "53") (name "SWO") (class "Default")
      (node (ref "CORTEX1") (pin "6") (pinfunction "SWO/TDO_6") (pintype "bidirectional"))
      (node (ref "U2") (pin "32") (pinfunction "P0.18/SWO_32") (pintype "bidirectional"))
    )
    (net (code "54") (name "TXD.FT") (class "Default")
      (node (ref "R1") (pin "1") (pinfunction "1_1") (pintype "passive"))
      (node (ref "U5") (pin "20") (pinfunction "TXD_20") (pintype "bidirectional"))
    )
    (net (code "55") (name "TXD.NRF") (class "Default")
      (node (ref "R2") (pin "2") (pinfunction "2_2") (pintype "passive"))
      (node (ref "U2") (pin "19") (pinfunction "P0.06_19") (pintype "bidirectional"))
    )
    (net (code "56") (name "USB+") (class "Default")
      (node (ref "C23") (pin "1") (pinfunction "1_1") (pintype "passive"))
      (node (ref "R18") (pin "1") (pinfunction "1_1") (pintype "passive"))
      (node (ref "USB2") (pin "3") (pinfunction "D+_3") (pintype "bidirectional"))
    )
    (net (code "57") (name "USB-") (class "Default")
      (node (ref "C24") (pin "2") (pinfunction "2_2") (pintype "passive"))
      (node (ref "R17") (pin "1") (pinfunction "1_1") (pintype "passive"))
      (node (ref "USB2") (pin "2") (pinfunction "D-_2") (pintype "bidirectional"))
    )
    (net (code "58") (name "VIN") (class "Default")
      (node (ref "C21") (pin "2") (pinfunction "2_2") (pintype "passive"))
      (node (ref "C5") (pin "2") (pinfunction "2_2") (pintype "passive"))
      (node (ref "CHRG2") (pin "4") (pinfunction "VIN_4") (pintype "power_in"))
      (node (ref "D4") (pin "-") (pinfunction "C_-") (pintype "passive"))
      (node (ref "D5") (pin "-") (pinfunction "C_-") (pintype "passive"))
      (node (ref "LDO2") (pin "1") (pinfunction "IN_1") (pintype "bidirectional"))
      (node (ref "LDO2") (pin "3") (pinfunction "EN_3") (pintype "bidirectional"))
      (node (ref "R12") (pin "2") (pinfunction "2_2") (pintype "passive"))
    )
    (net (code "59") (name "VLIPO") (class "Default")
      (node (ref "C20") (pin "1") (pinfunction "1_1") (pintype "passive"))
      (node (ref "CHRG2") (pin "3") (pinfunction "VBAT_3") (pintype "power_in"))
      (node (ref "D4") (pin "+") (pinfunction "A_+") (pintype "passive"))
      (node (ref "J2") (pin "2") (pinfunction "2_2") (pintype "passive"))
      (node (ref "R13") (pin "2") (pinfunction "2_2") (pintype "passive"))
    )
    (net (code "60") (name "VUSB") (class "Default")
      (node (ref "D5") (pin "+") (pinfunction "A_+") (pintype "passive"))
      (node (ref "U5") (pin "15") (pinfunction "VCC_15") (pintype "bidirectional"))
      (node (ref "USB2") (pin "1") (pinfunction "V+_1") (pintype "bidirectional"))
    )
    (net (code "61") (name "unconnected-(CORTEX1-NC{slash}TDI-Pad8)") (class "Default")
      (node (ref "CORTEX1") (pin "8") (pinfunction "NC/TDI_8") (pintype "bidirectional"))
    )
    (net (code "62") (name "unconnected-(J1-Pad1)") (class "Default")
      (node (ref "J1") (pin "1") (pinfunction "1_1") (pintype "passive"))
    )
    (net (code "63") (name "unconnected-(J1-Pad2)") (class "Default")
      (node (ref "J1") (pin "2") (pinfunction "2_2") (pintype "passive"))
    )
    (net (code "64") (name "unconnected-(J1-Pad3)") (class "Default")
      (node (ref "J1") (pin "3") (pinfunction "3_3") (pintype "passive"))
    )
    (net (code "65") (name "unconnected-(J1-Pad4)") (class "Default")
      (node (ref "J1") (pin "4") (pinfunction "4_4") (pintype "passive"))
    )
    (net (code "66") (name "unconnected-(J1-Pad5)") (class "Default")
      (node (ref "J1") (pin "5") (pinfunction "5_5") (pintype "passive"))
    )
    (net (code "67") (name "unconnected-(J1-Pad6)") (class "Default")
      (node (ref "J1") (pin "6") (pinfunction "6_6") (pintype "passive"))
    )
    (net (code "68") (name "unconnected-(SW1-2-PadA2)") (class "Default")
      (node (ref "SW1") (pin "A2") (pinfunction "2_A2") (pintype "passive"))
    )
    (net (code "69") (name "unconnected-(SW2-2-PadA2)") (class "Default")
      (node (ref "SW2") (pin "A2") (pinfunction "2_A2") (pintype "passive"))
    )
    (net (code "70") (name "unconnected-(U2-P0.02{slash}AIN0-Pad15)") (class "Default")
      (node (ref "U2") (pin "15") (pinfunction "P0.02/AIN0_15") (pintype "bidirectional"))
    )
    (net (code "71") (name "unconnected-(U2-P0.05{slash}AIN3-Pad18)") (class "Default")
      (node (ref "U2") (pin "18") (pinfunction "P0.05/AIN3_18") (pintype "bidirectional"))
    )
    (net (code "72") (name "unconnected-(U2-P0.07-Pad20)") (class "Default")
      (node (ref "U2") (pin "20") (pinfunction "P0.07_20") (pintype "bidirectional"))
    )
    (net (code "73") (name "unconnected-(U2-P0.23-Pad41)") (class "Default")
      (node (ref "U2") (pin "41") (pinfunction "P0.23_41") (pintype "bidirectional"))
    )
    (net (code "74") (name "unconnected-(U2-P0.24-Pad40)") (class "Default")
      (node (ref "U2") (pin "40") (pinfunction "P0.24_40") (pintype "bidirectional"))
    )
    (net (code "75") (name "unconnected-(U3-D2{slash}I2C_SDA-Pad20)") (class "Default")
      (node (ref "U3") (pin "20") (pinfunction "D2/I2C_SDA_20") (pintype "bidirectional"))
    )
    (net (code "76") (name "unconnected-(U3-D3-Pad21)") (class "Default")
      (node (ref "U3") (pin "21") (pinfunction "D3_21") (pintype "bidirectional"))
    )
    (net (code "77") (name "unconnected-(U3-D4-Pad22)") (class "Default")
      (node (ref "U3") (pin "22") (pinfunction "D4_22") (pintype "bidirectional"))
    )
    (net (code "78") (name "unconnected-(U3-D5-Pad23)") (class "Default")
      (node (ref "U3") (pin "23") (pinfunction "D5_23") (pintype "bidirectional"))
    )
    (net (code "79") (name "unconnected-(U3-D6-Pad24)") (class "Default")
      (node (ref "U3") (pin "24") (pinfunction "D6_24") (pintype "bidirectional"))
    )
    (net (code "80") (name "unconnected-(U3-D7-Pad25)") (class "Default")
      (node (ref "U3") (pin "25") (pinfunction "D7_25") (pintype "bidirectional"))
    )
    (net (code "81") (name "unconnected-(U3-E{slash}RD-Pad17)") (class "Default")
      (node (ref "U3") (pin "17") (pinfunction "E/RD_17") (pintype "input"))
    )
    (net (code "82") (name "unconnected-(U3-NC-Pad7)") (class "Default")
      (node (ref "U3") (pin "7") (pinfunction "NC_7") (pintype "no_connect"))
    )
    (net (code "83") (name "unconnected-(U3-R{slash}W-Pad16)") (class "Default")
      (node (ref "U3") (pin "16") (pinfunction "R/W_16") (pintype "input"))
    )
    (net (code "84") (name "unconnected-(U5-CBUS0-Pad18)") (class "Default")
      (node (ref "U5") (pin "18") (pinfunction "CBUS0_18") (pintype "bidirectional"))
    )
    (net (code "85") (name "unconnected-(U5-CBUS3-Pad19)") (class "Default")
      (node (ref "U5") (pin "19") (pinfunction "CBUS3_19") (pintype "bidirectional"))
    )
    (net (code "86") (name "unconnected-(U5-~{DCD}-Pad8)") (class "Default")
      (node (ref "U5") (pin "8") (pinfunction "~{DCD}_8") (pintype "bidirectional"))
    )
    (net (code "87") (name "unconnected-(U5-~{DSR}-Pad7)") (class "Default")
      (node (ref "U5") (pin "7") (pinfunction "~{DSR}_7") (pintype "bidirectional"))
    )
    (net (code "88") (name "unconnected-(U5-~{RI}-Pad5)") (class "Default")
      (node (ref "U5") (pin "5") (pinfunction "~{RI}_5") (pintype "bidirectional"))
    )
    (net (code "89") (name "unconnected-(U5-~{RTS}-Pad2)") (class "Default")
      (node (ref "U5") (pin "2") (pinfunction "~{RTS}_2") (pintype "bidirectional"))
    )
    (net (code "90") (name "unconnected-(USB2-ID-Pad4)") (class "Default")
      (node (ref "USB2") (pin "4") (pinfunction "ID_4") (pintype "bidirectional"))
    )
  )
)
